# Garage_Controller.net
KiCad netlist of a schematic drawn in EAGLE
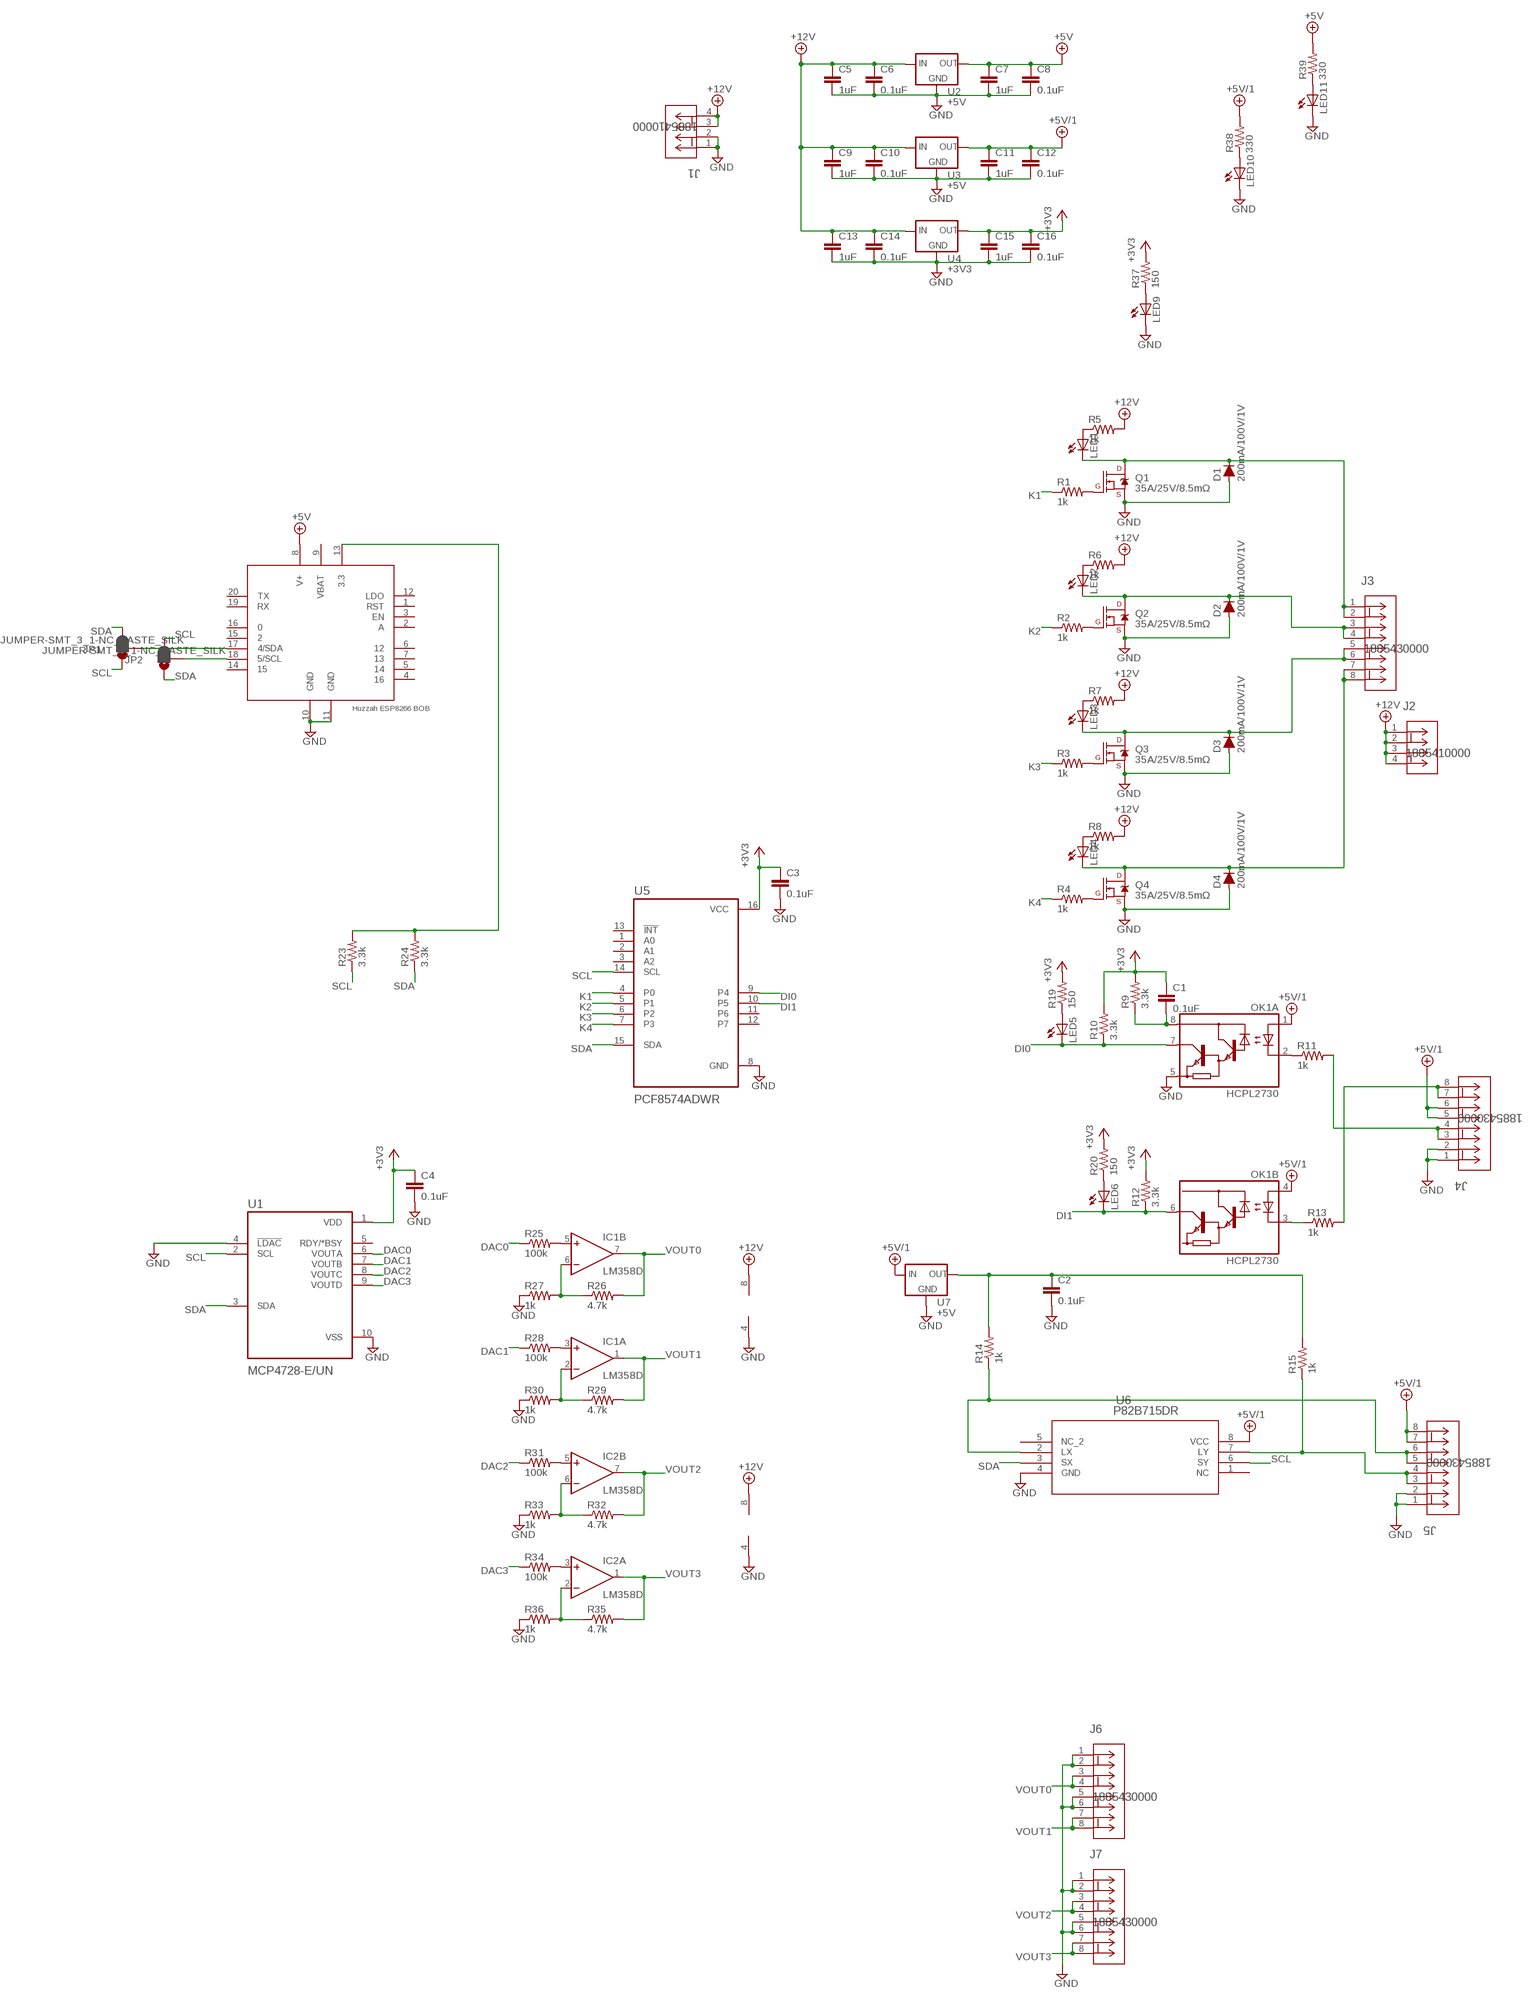
[diagram p0: schematic, sheet 1]

(export (version "E")
  (design (tool "Eeschema 10.0.6"))
  (components
    (comp (ref "C1")
      (value "0.1uF")
      (footprint "eagle-import:C0805")
      (libsource (lib "eagle-import") (part "C-EUC0805"))
    )
    (comp (ref "C2")
      (value "0.1uF")
      (footprint "eagle-import:C0805")
      (libsource (lib "eagle-import") (part "C-EUC0805"))
    )
    (comp (ref "C3")
      (value "0.1uF")
      (footprint "eagle-import:C0805")
      (libsource (lib "eagle-import") (part "C-EUC0805"))
    )
    (comp (ref "C4")
      (value "0.1uF")
      (footprint "eagle-import:C0805")
      (libsource (lib "eagle-import") (part "C-EUC0805"))
    )
    (comp (ref "C5")
      (value "1uF")
      (footprint "eagle-import:C0805")
      (libsource (lib "eagle-import") (part "C-EUC0805"))
    )
    (comp (ref "C6")
      (value "0.1uF")
      (footprint "eagle-import:C0805")
      (libsource (lib "eagle-import") (part "C-EUC0805"))
    )
    (comp (ref "C7")
      (value "1uF")
      (footprint "eagle-import:C0805")
      (libsource (lib "eagle-import") (part "C-EUC0805"))
    )
    (comp (ref "C8")
      (value "0.1uF")
      (footprint "eagle-import:C0805")
      (libsource (lib "eagle-import") (part "C-EUC0805"))
    )
    (comp (ref "C9")
      (value "1uF")
      (footprint "eagle-import:C0805")
      (libsource (lib "eagle-import") (part "C-EUC0805"))
    )
    (comp (ref "C10")
      (value "0.1uF")
      (footprint "eagle-import:C0805")
      (libsource (lib "eagle-import") (part "C-EUC0805"))
    )
    (comp (ref "C11")
      (value "1uF")
      (footprint "eagle-import:C0805")
      (libsource (lib "eagle-import") (part "C-EUC0805"))
    )
    (comp (ref "C12")
      (value "0.1uF")
      (footprint "eagle-import:C0805")
      (libsource (lib "eagle-import") (part "C-EUC0805"))
    )
    (comp (ref "C13")
      (value "1uF")
      (footprint "eagle-import:C0805")
      (libsource (lib "eagle-import") (part "C-EUC0805"))
    )
    (comp (ref "C14")
      (value "0.1uF")
      (footprint "eagle-import:C0805")
      (libsource (lib "eagle-import") (part "C-EUC0805"))
    )
    (comp (ref "C15")
      (value "1uF")
      (footprint "eagle-import:C0805")
      (libsource (lib "eagle-import") (part "C-EUC0805"))
    )
    (comp (ref "C16")
      (value "0.1uF")
      (footprint "eagle-import:C0805")
      (libsource (lib "eagle-import") (part "C-EUC0805"))
    )
    (comp (ref "D1")
      (value "200mA/100V/1V")
      (footprint "eagle-import:DIODE-1N4148")
      (libsource (lib "eagle-import") (part "DIODE-1N4148"))
    )
    (comp (ref "D2")
      (value "200mA/100V/1V")
      (footprint "eagle-import:DIODE-1N4148")
      (libsource (lib "eagle-import") (part "DIODE-1N4148"))
    )
    (comp (ref "D3")
      (value "200mA/100V/1V")
      (footprint "eagle-import:DIODE-1N4148")
      (libsource (lib "eagle-import") (part "DIODE-1N4148"))
    )
    (comp (ref "D4")
      (value "200mA/100V/1V")
      (footprint "eagle-import:DIODE-1N4148")
      (libsource (lib "eagle-import") (part "DIODE-1N4148"))
    )
    (comp (ref "IC1")
      (value "LM358D")
      (footprint "eagle-import:SO08")
      (libsource (lib "eagle-import") (part "LM358D"))
    )
    (comp (ref "IC2")
      (value "LM358D")
      (footprint "eagle-import:SO08")
      (libsource (lib "eagle-import") (part "LM358D"))
    )
    (comp (ref "J1")
      (value "1885410000")
      (footprint "eagle-import:CONN_1885410000_WED")
      (fields (field (name "COPYRIGHT") "Copyright (C) 2026 Ultra Librarian. All rights reserved."))
      (libsource (lib "eagle-import") (part "1885410000"))
    )
    (comp (ref "J2")
      (value "1885410000")
      (footprint "eagle-import:CONN_1885410000_WED")
      (fields (field (name "COPYRIGHT") "Copyright (C) 2026 Ultra Librarian. All rights reserved."))
      (libsource (lib "eagle-import") (part "1885410000"))
    )
    (comp (ref "J3")
      (value "1885430000")
      (footprint "eagle-import:CONN_1885430000_WED")
      (fields (field (name "COPYRIGHT") "Copyright (C) 2026 Ultra Librarian. All rights reserved."))
      (libsource (lib "eagle-import") (part "1885430000"))
    )
    (comp (ref "J4")
      (value "1885430000")
      (footprint "eagle-import:CONN_1885430000_WED")
      (fields (field (name "COPYRIGHT") "Copyright (C) 2026 Ultra Librarian. All rights reserved."))
      (libsource (lib "eagle-import") (part "1885430000"))
    )
    (comp (ref "J5")
      (value "1885430000")
      (footprint "eagle-import:CONN_1885430000_WED")
      (fields (field (name "COPYRIGHT") "Copyright (C) 2026 Ultra Librarian. All rights reserved."))
      (libsource (lib "eagle-import") (part "1885430000"))
    )
    (comp (ref "J6")
      (value "1885430000")
      (footprint "eagle-import:CONN_1885430000_WED")
      (fields (field (name "COPYRIGHT") "Copyright (C) 2026 Ultra Librarian. All rights reserved."))
      (libsource (lib "eagle-import") (part "1885430000"))
    )
    (comp (ref "J7")
      (value "1885430000")
      (footprint "eagle-import:CONN_1885430000_WED")
      (fields (field (name "COPYRIGHT") "Copyright (C) 2026 Ultra Librarian. All rights reserved."))
      (libsource (lib "eagle-import") (part "1885430000"))
    )
    (comp (ref "JP1")
      (value "JUMPER-SMT_3_1-NC_PASTE_SILK")
      (footprint "eagle-import:SMT-JUMPER_3_1-NC_PASTE_SILK")
      (libsource (lib "eagle-import") (part "JUMPER-SMT_3_1-NC_PASTE_SILK"))
    )
    (comp (ref "JP2")
      (value "JUMPER-SMT_3_1-NC_PASTE_SILK")
      (footprint "eagle-import:SMT-JUMPER_3_1-NC_PASTE_SILK")
      (libsource (lib "eagle-import") (part "JUMPER-SMT_3_1-NC_PASTE_SILK"))
    )
    (comp (ref "LED1")
      (value "LEDCHIP-LED0805")
      (footprint "eagle-import:CHIP-LED0805")
      (libsource (lib "eagle-import") (part "LEDCHIP-LED0805"))
    )
    (comp (ref "LED2")
      (value "LEDCHIP-LED0805")
      (footprint "eagle-import:CHIP-LED0805")
      (libsource (lib "eagle-import") (part "LEDCHIP-LED0805"))
    )
    (comp (ref "LED3")
      (value "LEDCHIP-LED0805")
      (footprint "eagle-import:CHIP-LED0805")
      (libsource (lib "eagle-import") (part "LEDCHIP-LED0805"))
    )
    (comp (ref "LED4")
      (value "LEDCHIP-LED0805")
      (footprint "eagle-import:CHIP-LED0805")
      (libsource (lib "eagle-import") (part "LEDCHIP-LED0805"))
    )
    (comp (ref "LED5")
      (value "LEDCHIP-LED0805")
      (footprint "eagle-import:CHIP-LED0805")
      (libsource (lib "eagle-import") (part "LEDCHIP-LED0805"))
    )
    (comp (ref "LED6")
      (value "LEDCHIP-LED0805")
      (footprint "eagle-import:CHIP-LED0805")
      (libsource (lib "eagle-import") (part "LEDCHIP-LED0805"))
    )
    (comp (ref "LED9")
      (value "LEDCHIP-LED0805")
      (footprint "eagle-import:CHIP-LED0805")
      (libsource (lib "eagle-import") (part "LEDCHIP-LED0805"))
    )
    (comp (ref "LED10")
      (value "LEDCHIP-LED0805")
      (footprint "eagle-import:CHIP-LED0805")
      (libsource (lib "eagle-import") (part "LEDCHIP-LED0805"))
    )
    (comp (ref "LED11")
      (value "LEDCHIP-LED0805")
      (footprint "eagle-import:CHIP-LED0805")
      (libsource (lib "eagle-import") (part "LEDCHIP-LED0805"))
    )
    (comp (ref "OK1")
      (value "HCPL2730")
      (footprint "eagle-import:DIL08")
      (fields (field (name "MF") "AGILENT TECHNOLOGIES") (field (name "MPN") "HCPL-2730-000E"))
      (libsource (lib "eagle-import") (part "HCPL2730"))
    )
    (comp (ref "Q1")
      (value "35A/25V/8.5mΩ")
      (footprint "eagle-import:TO-252_DPAK")
      (libsource (lib "eagle-import") (part "MOSFET-NCH-FDD8780"))
    )
    (comp (ref "Q2")
      (value "35A/25V/8.5mΩ")
      (footprint "eagle-import:TO-252_DPAK")
      (libsource (lib "eagle-import") (part "MOSFET-NCH-FDD8780"))
    )
    (comp (ref "Q3")
      (value "35A/25V/8.5mΩ")
      (footprint "eagle-import:TO-252_DPAK")
      (libsource (lib "eagle-import") (part "MOSFET-NCH-FDD8780"))
    )
    (comp (ref "Q4")
      (value "35A/25V/8.5mΩ")
      (footprint "eagle-import:TO-252_DPAK")
      (libsource (lib "eagle-import") (part "MOSFET-NCH-FDD8780"))
    )
    (comp (ref "R1")
      (value "1k")
      (footprint "eagle-import:R0805")
      (libsource (lib "eagle-import") (part "R-US_R0805"))
    )
    (comp (ref "R2")
      (value "1k")
      (footprint "eagle-import:R0805")
      (libsource (lib "eagle-import") (part "R-US_R0805"))
    )
    (comp (ref "R3")
      (value "1k")
      (footprint "eagle-import:R0805")
      (libsource (lib "eagle-import") (part "R-US_R0805"))
    )
    (comp (ref "R4")
      (value "1k")
      (footprint "eagle-import:R0805")
      (libsource (lib "eagle-import") (part "R-US_R0805"))
    )
    (comp (ref "R5")
      (value "1k")
      (footprint "eagle-import:R0805")
      (libsource (lib "eagle-import") (part "R-US_R0805"))
    )
    (comp (ref "R6")
      (value "1k")
      (footprint "eagle-import:R0805")
      (libsource (lib "eagle-import") (part "R-US_R0805"))
    )
    (comp (ref "R7")
      (value "1k")
      (footprint "eagle-import:R0805")
      (libsource (lib "eagle-import") (part "R-US_R0805"))
    )
    (comp (ref "R8")
      (value "1k")
      (footprint "eagle-import:R0805")
      (libsource (lib "eagle-import") (part "R-US_R0805"))
    )
    (comp (ref "R9")
      (value "3.3k")
      (footprint "eagle-import:R0805")
      (libsource (lib "eagle-import") (part "R-US_R0805"))
    )
    (comp (ref "R10")
      (value "3.3k")
      (footprint "eagle-import:R0805")
      (libsource (lib "eagle-import") (part "R-US_R0805"))
    )
    (comp (ref "R11")
      (value "1k")
      (footprint "eagle-import:R0805")
      (libsource (lib "eagle-import") (part "R-US_R0805"))
    )
    (comp (ref "R12")
      (value "3.3k")
      (footprint "eagle-import:R0805")
      (libsource (lib "eagle-import") (part "R-US_R0805"))
    )
    (comp (ref "R13")
      (value "1k")
      (footprint "eagle-import:R0805")
      (libsource (lib "eagle-import") (part "R-US_R0805"))
    )
    (comp (ref "R14")
      (value "1k")
      (footprint "eagle-import:R0805")
      (libsource (lib "eagle-import") (part "R-US_R0805"))
    )
    (comp (ref "R15")
      (value "1k")
      (footprint "eagle-import:R0805")
      (libsource (lib "eagle-import") (part "R-US_R0805"))
    )
    (comp (ref "R19")
      (value "150")
      (footprint "eagle-import:R0805")
      (libsource (lib "eagle-import") (part "R-US_R0805"))
    )
    (comp (ref "R20")
      (value "150")
      (footprint "eagle-import:R0805")
      (libsource (lib "eagle-import") (part "R-US_R0805"))
    )
    (comp (ref "R23")
      (value "3.3k")
      (footprint "eagle-import:R0805")
      (libsource (lib "eagle-import") (part "R-US_R0805"))
    )
    (comp (ref "R24")
      (value "3.3k")
      (footprint "eagle-import:R0805")
      (libsource (lib "eagle-import") (part "R-US_R0805"))
    )
    (comp (ref "R25")
      (value "100k")
      (footprint "eagle-import:R0805")
      (libsource (lib "eagle-import") (part "R-US_R0805"))
    )
    (comp (ref "R26")
      (value "4.7k")
      (footprint "eagle-import:R0805")
      (libsource (lib "eagle-import") (part "R-US_R0805"))
    )
    (comp (ref "R27")
      (value "1k")
      (footprint "eagle-import:R0805")
      (libsource (lib "eagle-import") (part "R-US_R0805"))
    )
    (comp (ref "R28")
      (value "100k")
      (footprint "eagle-import:R0805")
      (libsource (lib "eagle-import") (part "R-US_R0805"))
    )
    (comp (ref "R29")
      (value "4.7k")
      (footprint "eagle-import:R0805")
      (libsource (lib "eagle-import") (part "R-US_R0805"))
    )
    (comp (ref "R30")
      (value "1k")
      (footprint "eagle-import:R0805")
      (libsource (lib "eagle-import") (part "R-US_R0805"))
    )
    (comp (ref "R31")
      (value "100k")
      (footprint "eagle-import:R0805")
      (libsource (lib "eagle-import") (part "R-US_R0805"))
    )
    (comp (ref "R32")
      (value "4.7k")
      (footprint "eagle-import:R0805")
      (libsource (lib "eagle-import") (part "R-US_R0805"))
    )
    (comp (ref "R33")
      (value "1k")
      (footprint "eagle-import:R0805")
      (libsource (lib "eagle-import") (part "R-US_R0805"))
    )
    (comp (ref "R34")
      (value "100k")
      (footprint "eagle-import:R0805")
      (libsource (lib "eagle-import") (part "R-US_R0805"))
    )
    (comp (ref "R35")
      (value "4.7k")
      (footprint "eagle-import:R0805")
      (libsource (lib "eagle-import") (part "R-US_R0805"))
    )
    (comp (ref "R36")
      (value "1k")
      (footprint "eagle-import:R0805")
      (libsource (lib "eagle-import") (part "R-US_R0805"))
    )
    (comp (ref "R37")
      (value "150")
      (footprint "eagle-import:R0805")
      (libsource (lib "eagle-import") (part "R-US_R0805"))
    )
    (comp (ref "R38")
      (value "330")
      (footprint "eagle-import:R0805")
      (libsource (lib "eagle-import") (part "R-US_R0805"))
    )
    (comp (ref "R39")
      (value "330")
      (footprint "eagle-import:R0805")
      (libsource (lib "eagle-import") (part "R-US_R0805"))
    )
    (comp (ref "U$2")
      (value "HUZZAH_ESP8266_BREAKOUT")
      (footprint "eagle-import:HUZZAH_ESP8266_BREAKOUT")
      (libsource (lib "eagle-import") (part "HUZZAH_ESP8266_BREAKOUT"))
    )
    (comp (ref "U1")
      (value "MCP4728-E/UN")
      (footprint "eagle-import:SOP50P490X110-10N")
      (libsource (lib "eagle-import") (part "MCP4728-E/UN"))
    )
    (comp (ref "U2")
      (value "+5V")
      (footprint "eagle-import:TO-252")
      (libsource (lib "eagle-import") (part "V_REG_78XX7812"))
    )
    (comp (ref "U3")
      (value "+5V")
      (footprint "eagle-import:TO-252")
      (libsource (lib "eagle-import") (part "V_REG_78XX7812"))
    )
    (comp (ref "U4")
      (value "+3V3")
      (footprint "eagle-import:TO-252")
      (libsource (lib "eagle-import") (part "V_REG_78XX7812"))
    )
    (comp (ref "U5")
      (value "PCF8574ADWR")
      (footprint "eagle-import:SOIC127P1030X265-16N")
      (libsource (lib "eagle-import") (part "PCF8574ADWR"))
    )
    (comp (ref "U6")
      (value "P82B715DR")
      (footprint "eagle-import:SO-08")
      (libsource (lib "eagle-import") (part "P82B715DR"))
    )
    (comp (ref "U7")
      (value "+5V")
      (footprint "eagle-import:TO-252")
      (libsource (lib "eagle-import") (part "V_REG_78XX7812"))
    )
  )
  (nets
    (net (code "1") (name "+3V3") (class "Default")
      (node (ref "C1") (pin "1") (pinfunction "1_1") (pintype "passive"))
      (node (ref "C15") (pin "1") (pinfunction "1_1") (pintype "passive"))
      (node (ref "C16") (pin "1") (pinfunction "1_1") (pintype "passive"))
      (node (ref "C3") (pin "1") (pinfunction "1_1") (pintype "passive"))
      (node (ref "C4") (pin "1") (pinfunction "1_1") (pintype "passive"))
      (node (ref "R10") (pin "2") (pinfunction "2_2") (pintype "passive"))
      (node (ref "R12") (pin "2") (pinfunction "2_2") (pintype "passive"))
      (node (ref "R19") (pin "2") (pinfunction "2_2") (pintype "passive"))
      (node (ref "R20") (pin "2") (pinfunction "2_2") (pintype "passive"))
      (node (ref "R37") (pin "2") (pinfunction "2_2") (pintype "passive"))
      (node (ref "R9") (pin "2") (pinfunction "2_2") (pintype "passive"))
      (node (ref "U1") (pin "1") (pinfunction "VDD_1") (pintype "power_in"))
      (node (ref "U4") (pin "2") (pinfunction "OUT_2") (pintype "passive"))
      (node (ref "U5") (pin "16") (pinfunction "VCC_16") (pintype "power_in"))
    )
    (net (code "2") (name "+5V") (class "Default")
      (node (ref "C7") (pin "1") (pinfunction "1_1") (pintype "passive"))
      (node (ref "C8") (pin "1") (pinfunction "1_1") (pintype "passive"))
      (node (ref "R39") (pin "2") (pinfunction "2_2") (pintype "passive"))
      (node (ref "U$2") (pin "8") (pinfunction "V+_8") (pintype "power_in"))
      (node (ref "U2") (pin "2") (pinfunction "OUT_2") (pintype "passive"))
    )
    (net (code "3") (name "+5V{slash}1") (class "Default")
      (node (ref "C11") (pin "1") (pinfunction "1_1") (pintype "passive"))
      (node (ref "C12") (pin "1") (pinfunction "1_1") (pintype "passive"))
      (node (ref "J4") (pin "5") (pinfunction "5_5") (pintype "passive"))
      (node (ref "J4") (pin "6") (pinfunction "6_6") (pintype "passive"))
      (node (ref "J5") (pin "7") (pinfunction "7_7") (pintype "passive"))
      (node (ref "J5") (pin "8") (pinfunction "8_8") (pintype "passive"))
      (node (ref "OK1") (pin "1") (pinfunction "A1_1") (pintype "passive"))
      (node (ref "OK1") (pin "4") (pinfunction "A2_4") (pintype "passive"))
      (node (ref "R38") (pin "2") (pinfunction "2_2") (pintype "passive"))
      (node (ref "U3") (pin "2") (pinfunction "OUT_2") (pintype "passive"))
      (node (ref "U6") (pin "8") (pinfunction "VCC_8") (pintype "power_in"))
      (node (ref "U7") (pin "1") (pinfunction "IN_1") (pintype "input"))
    )
    (net (code "4") (name "+12V") (class "Default")
      (node (ref "C10") (pin "1") (pinfunction "1_1") (pintype "passive"))
      (node (ref "C13") (pin "1") (pinfunction "1_1") (pintype "passive"))
      (node (ref "C14") (pin "1") (pinfunction "1_1") (pintype "passive"))
      (node (ref "C5") (pin "1") (pinfunction "1_1") (pintype "passive"))
      (node (ref "C6") (pin "1") (pinfunction "1_1") (pintype "passive"))
      (node (ref "C9") (pin "1") (pinfunction "1_1") (pintype "passive"))
      (node (ref "IC1") (pin "8") (pinfunction "V+_8") (pintype "power_in"))
      (node (ref "IC2") (pin "8") (pinfunction "V+_8") (pintype "power_in"))
      (node (ref "J1") (pin "3") (pinfunction "3_3") (pintype "passive"))
      (node (ref "J1") (pin "4") (pinfunction "4_4") (pintype "passive"))
      (node (ref "J2") (pin "1") (pinfunction "1_1") (pintype "passive"))
      (node (ref "J2") (pin "2") (pinfunction "2_2") (pintype "passive"))
      (node (ref "J2") (pin "3") (pinfunction "3_3") (pintype "passive"))
      (node (ref "J2") (pin "4") (pinfunction "4_4") (pintype "passive"))
      (node (ref "R5") (pin "2") (pinfunction "2_2") (pintype "passive"))
      (node (ref "R6") (pin "2") (pinfunction "2_2") (pintype "passive"))
      (node (ref "R7") (pin "2") (pinfunction "2_2") (pintype "passive"))
      (node (ref "R8") (pin "2") (pinfunction "2_2") (pintype "passive"))
      (node (ref "U2") (pin "1") (pinfunction "IN_1") (pintype "input"))
      (node (ref "U3") (pin "1") (pinfunction "IN_1") (pintype "input"))
      (node (ref "U4") (pin "1") (pinfunction "IN_1") (pintype "input"))
    )
    (net (code "5") (name "/DAC0") (class "Default")
      (node (ref "R25") (pin "1") (pinfunction "1_1") (pintype "passive"))
      (node (ref "U1") (pin "6") (pinfunction "VOUTA_6") (pintype "output"))
    )
    (net (code "6") (name "/DAC1") (class "Default")
      (node (ref "R28") (pin "1") (pinfunction "1_1") (pintype "passive"))
      (node (ref "U1") (pin "7") (pinfunction "VOUTB_7") (pintype "output"))
    )
    (net (code "7") (name "/DAC2") (class "Default")
      (node (ref "R31") (pin "1") (pinfunction "1_1") (pintype "passive"))
      (node (ref "U1") (pin "8") (pinfunction "VOUTC_8") (pintype "output"))
    )
    (net (code "8") (name "/DAC3") (class "Default")
      (node (ref "R34") (pin "1") (pinfunction "1_1") (pintype "passive"))
      (node (ref "U1") (pin "9") (pinfunction "VOUTD_9") (pintype "output"))
    )
    (net (code "9") (name "/DI0") (class "Default")
      (node (ref "LED5") (pin "C") (pinfunction "C_C") (pintype "passive"))
      (node (ref "OK1") (pin "7") (pinfunction "VO1_7") (pintype "passive"))
      (node (ref "R10") (pin "1") (pinfunction "1_1") (pintype "passive"))
      (node (ref "U5") (pin "9") (pinfunction "P4_9") (pintype "bidirectional"))
    )
    (net (code "10") (name "/DI1") (class "Default")
      (node (ref "LED6") (pin "C") (pinfunction "C_C") (pintype "passive"))
      (node (ref "OK1") (pin "6") (pinfunction "VO2_6") (pintype "passive"))
      (node (ref "R12") (pin "1") (pinfunction "1_1") (pintype "passive"))
      (node (ref "U5") (pin "10") (pinfunction "P5_10") (pintype "bidirectional"))
    )
    (net (code "11") (name "/K1") (class "Default")
      (node (ref "R1") (pin "1") (pinfunction "1_1") (pintype "passive"))
      (node (ref "U5") (pin "4") (pinfunction "P0_4") (pintype "bidirectional"))
    )
    (net (code "12") (name "/K2") (class "Default")
      (node (ref "R2") (pin "1") (pinfunction "1_1") (pintype "passive"))
      (node (ref "U5") (pin "5") (pinfunction "P1_5") (pintype "bidirectional"))
    )
    (net (code "13") (name "/K3") (class "Default")
      (node (ref "R3") (pin "1") (pinfunction "1_1") (pintype "passive"))
      (node (ref "U5") (pin "6") (pinfunction "P2_6") (pintype "bidirectional"))
    )
    (net (code "14") (name "/K4") (class "Default")
      (node (ref "R4") (pin "1") (pinfunction "1_1") (pintype "passive"))
      (node (ref "U5") (pin "7") (pinfunction "P3_7") (pintype "bidirectional"))
    )
    (net (code "15") (name "/SCL") (class "Default")
      (node (ref "JP1") (pin "1") (pinfunction "1_1") (pintype "passive"))
      (node (ref "JP2") (pin "3") (pinfunction "3_3") (pintype "passive"))
      (node (ref "R23") (pin "1") (pinfunction "1_1") (pintype "passive"))
      (node (ref "U1") (pin "2") (pinfunction "SCL_2") (pintype "input"))
      (node (ref "U5") (pin "14") (pinfunction "SCL_14") (pintype "input"))
      (node (ref "U6") (pin "6") (pinfunction "SY_6") (pintype "passive"))
    )
    (net (code "16") (name "/SDA") (class "Default")
      (node (ref "JP1") (pin "3") (pinfunction "3_3") (pintype "passive"))
      (node (ref "JP2") (pin "1") (pinfunction "1_1") (pintype "passive"))
      (node (ref "R24") (pin "1") (pinfunction "1_1") (pintype "passive"))
      (node (ref "U1") (pin "3") (pinfunction "SDA_3") (pintype "bidirectional"))
      (node (ref "U5") (pin "15") (pinfunction "SDA_15") (pintype "bidirectional"))
      (node (ref "U6") (pin "3") (pinfunction "SX_3") (pintype "passive"))
    )
    (net (code "17") (name "/VBAT") (class "Default")
      (node (ref "U$2") (pin "9") (pinfunction "VBAT_9") (pintype "power_in"))
    )
    (net (code "18") (name "/VOUT0") (class "Default")
      (node (ref "IC1") (pin "7") (pinfunction "OUT_7") (pintype "output"))
      (node (ref "J6") (pin "3") (pinfunction "3_3") (pintype "passive"))
      (node (ref "J6") (pin "4") (pinfunction "4_4") (pintype "passive"))
      (node (ref "R26") (pin "2") (pinfunction "2_2") (pintype "passive"))
    )
    (net (code "19") (name "/VOUT1") (class "Default")
      (node (ref "IC1") (pin "1") (pinfunction "OUT_1") (pintype "output"))
      (node (ref "J6") (pin "7") (pinfunction "7_7") (pintype "passive"))
      (node (ref "J6") (pin "8") (pinfunction "8_8") (pintype "passive"))
      (node (ref "R29") (pin "2") (pinfunction "2_2") (pintype "passive"))
    )
    (net (code "20") (name "/VOUT2") (class "Default")
      (node (ref "IC2") (pin "7") (pinfunction "OUT_7") (pintype "output"))
      (node (ref "J7") (pin "3") (pinfunction "3_3") (pintype "passive"))
      (node (ref "J7") (pin "4") (pinfunction "4_4") (pintype "passive"))
      (node (ref "R32") (pin "2") (pinfunction "2_2") (pintype "passive"))
    )
    (net (code "21") (name "/VOUT3") (class "Default")
      (node (ref "IC2") (pin "1") (pinfunction "OUT_1") (pintype "output"))
      (node (ref "J7") (pin "7") (pinfunction "7_7") (pintype "passive"))
      (node (ref "J7") (pin "8") (pinfunction "8_8") (pintype "passive"))
      (node (ref "R35") (pin "2") (pinfunction "2_2") (pintype "passive"))
    )
    (net (code "22") (name "GND") (class "Default")
      (node (ref "C10") (pin "2") (pinfunction "2_2") (pintype "passive"))
      (node (ref "C11") (pin "2") (pinfunction "2_2") (pintype "passive"))
      (node (ref "C12") (pin "2") (pinfunction "2_2") (pintype "passive"))
      (node (ref "C13") (pin "2") (pinfunction "2_2") (pintype "passive"))
      (node (ref "C14") (pin "2") (pinfunction "2_2") (pintype "passive"))
      (node (ref "C15") (pin "2") (pinfunction "2_2") (pintype "passive"))
      (node (ref "C16") (pin "2") (pinfunction "2_2") (pintype "passive"))
      (node (ref "C2") (pin "2") (pinfunction "2_2") (pintype "passive"))
      (node (ref "C3") (pin "2") (pinfunction "2_2") (pintype "passive"))
      (node (ref "C4") (pin "2") (pinfunction "2_2") (pintype "passive"))
      (node (ref "C5") (pin "2") (pinfunction "2_2") (pintype "passive"))
      (node (ref "C6") (pin "2") (pinfunction "2_2") (pintype "passive"))
      (node (ref "C7") (pin "2") (pinfunction "2_2") (pintype "passive"))
      (node (ref "C8") (pin "2") (pinfunction "2_2") (pintype "passive"))
      (node (ref "C9") (pin "2") (pinfunction "2_2") (pintype "passive"))
      (node (ref "D1") (pin "A") (pinfunction "A_A") (pintype "passive"))
      (node (ref "D2") (pin "A") (pinfunction "A_A") (pintype "passive"))
      (node (ref "D3") (pin "A") (pinfunction "A_A") (pintype "passive"))
      (node (ref "D4") (pin "A") (pinfunction "A_A") (pintype "passive"))
      (node (ref "IC1") (pin "4") (pinfunction "V-_4") (pintype "power_in"))
      (node (ref "IC2") (pin "4") (pinfunction "V-_4") (pintype "power_in"))
      (node (ref "J1") (pin "1") (pinfunction "1_1") (pintype "passive"))
      (node (ref "J1") (pin "2") (pinfunction "2_2") (pintype "passive"))
      (node (ref "J4") (pin "1") (pinfunction "1_1") (pintype "passive"))
      (node (ref "J4") (pin "2") (pinfunction "2_2") (pintype "passive"))
      (node (ref "J5") (pin "1") (pinfunction "1_1") (pintype "passive"))
      (node (ref "J5") (pin "2") (pinfunction "2_2") (pintype "passive"))
      (node (ref "J6") (pin "1") (pinfunction "1_1") (pintype "passive"))
      (node (ref "J6") (pin "2") (pinfunction "2_2") (pintype "passive"))
      (node (ref "J6") (pin "5") (pinfunction "5_5") (pintype "passive"))
      (node (ref "J6") (pin "6") (pinfunction "6_6") (pintype "passive"))
      (node (ref "J7") (pin "1") (pinfunction "1_1") (pintype "passive"))
      (node (ref "J7") (pin "2") (pinfunction "2_2") (pintype "passive"))
      (node (ref "J7") (pin "5") (pinfunction "5_5") (pintype "passive"))
      (node (ref "J7") (pin "6") (pinfunction "6_6") (pintype "passive"))
      (node (ref "LED10") (pin "C") (pinfunction "C_C") (pintype "passive"))
      (node (ref "LED11") (pin "C") (pinfunction "C_C") (pintype "passive"))
      (node (ref "LED9") (pin "C") (pinfunction "C_C") (pintype "passive"))
      (node (ref "OK1") (pin "5") (pinfunction "GND_5") (pintype "passive"))
      (node (ref "Q1") (pin "3") (pinfunction "S_3") (pintype "bidirectional"))
      (node (ref "Q2") (pin "3") (pinfunction "S_3") (pintype "bidirectional"))
      (node (ref "Q3") (pin "3") (pinfunction "S_3") (pintype "bidirectional"))
      (node (ref "Q4") (pin "3") (pinfunction "S_3") (pintype "bidirectional"))
      (node (ref "R27") (pin "1") (pinfunction "1_1") (pintype "passive"))
      (node (ref "R30") (pin "1") (pinfunction "1_1") (pintype "passive"))
      (node (ref "R33") (pin "1") (pinfunction "1_1") (pintype "passive"))
      (node (ref "R36") (pin "1") (pinfunction "1_1") (pintype "passive"))
      (node (ref "U$2") (pin "10") (pinfunction "GND_10") (pintype "power_in"))
      (node (ref "U$2") (pin "11") (pinfunction "GND_11") (pintype "power_in"))
      (node (ref "U1") (pin "10") (pinfunction "VSS_10") (pintype "power_in"))
      (node (ref "U1") (pin "4") (pinfunction "~{LDAC}_4") (pintype "input"))
      (node (ref "U2") (pin "3") (pinfunction "GND_3") (pintype "input"))
      (node (ref "U3") (pin "3") (pinfunction "GND_3") (pintype "input"))
      (node (ref "U4") (pin "3") (pinfunction "GND_3") (pintype "input"))
      (node (ref "U5") (pin "8") (pinfunction "GND_8") (pintype "power_in"))
      (node (ref "U6") (pin "4") (pinfunction "GND_4") (pintype "power_in"))
      (node (ref "U7") (pin "3") (pinfunction "GND_3") (pintype "input"))
    )
    (net (code "23") (name "Net-(IC1A-+IN)") (class "Default")
      (node (ref "IC1") (pin "3") (pinfunction "+IN_3") (pintype "input"))
      (node (ref "R28") (pin "2") (pinfunction "2_2") (pintype "passive"))
    )
    (net (code "24") (name "Net-(IC1A--IN)") (class "Default")
      (node (ref "IC1") (pin "2") (pinfunction "-IN_2") (pintype "input"))
      (node (ref "R29") (pin "1") (pinfunction "1_1") (pintype "passive"))
      (node (ref "R30") (pin "2") (pinfunction "2_2") (pintype "passive"))
    )
    (net (code "25") (name "Net-(IC1B-+IN)") (class "Default")
      (node (ref "IC1") (pin "5") (pinfunction "+IN_5") (pintype "input"))
      (node (ref "R25") (pin "2") (pinfunction "2_2") (pintype "passive"))
    )
    (net (code "26") (name "Net-(IC1B--IN)") (class "Default")
      (node (ref "IC1") (pin "6") (pinfunction "-IN_6") (pintype "input"))
      (node (ref "R26") (pin "1") (pinfunction "1_1") (pintype "passive"))
      (node (ref "R27") (pin "2") (pinfunction "2_2") (pintype "passive"))
    )
    (net (code "27") (name "Net-(IC2A-+IN)") (class "Default")
      (node (ref "IC2") (pin "3") (pinfunction "+IN_3") (pintype "input"))
      (node (ref "R34") (pin "2") (pinfunction "2_2") (pintype "passive"))
    )
    (net (code "28") (name "Net-(IC2A--IN)") (class "Default")
      (node (ref "IC2") (pin "2") (pinfunction "-IN_2") (pintype "input"))
      (node (ref "R35") (pin "1") (pinfunction "1_1") (pintype "passive"))
      (node (ref "R36") (pin "2") (pinfunction "2_2") (pintype "passive"))
    )
    (net (code "29") (name "Net-(IC2B-+IN)") (class "Default")
      (node (ref "IC2") (pin "5") (pinfunction "+IN_5") (pintype "input"))
      (node (ref "R31") (pin "2") (pinfunction "2_2") (pintype "passive"))
    )
    (net (code "30") (name "Net-(IC2B--IN)") (class "Default")
      (node (ref "IC2") (pin "6") (pinfunction "-IN_6") (pintype "input"))
      (node (ref "R32") (pin "1") (pinfunction "1_1") (pintype "passive"))
      (node (ref "R33") (pin "2") (pinfunction "2_2") (pintype "passive"))
    )
    (net (code "31") (name "Net-(J4-Pad3)") (class "Default")
      (node (ref "J4") (pin "3") (pinfunction "3_3") (pintype "passive"))
      (node (ref "J4") (pin "4") (pinfunction "4_4") (pintype "passive"))
      (node (ref "R11") (pin "2") (pinfunction "2_2") (pintype "passive"))
    )
    (net (code "32") (name "Net-(J4-Pad7)") (class "Default")
      (node (ref "J4") (pin "7") (pinfunction "7_7") (pintype "passive"))
      (node (ref "J4") (pin "8") (pinfunction "8_8") (pintype "passive"))
      (node (ref "R13") (pin "2") (pinfunction "2_2") (pintype "passive"))
    )
    (net (code "33") (name "Net-(LED1-PadA)") (class "Default")
      (node (ref "LED1") (pin "A") (pinfunction "A_A") (pintype "passive"))
      (node (ref "R5") (pin "1") (pinfunction "1_1") (pintype "passive"))
    )
    (net (code "34") (name "Net-(LED2-PadA)") (class "Default")
      (node (ref "LED2") (pin "A") (pinfunction "A_A") (pintype "passive"))
      (node (ref "R6") (pin "1") (pinfunction "1_1") (pintype "passive"))
    )
    (net (code "35") (name "Net-(LED3-PadA)") (class "Default")
      (node (ref "LED3") (pin "A") (pinfunction "A_A") (pintype "passive"))
      (node (ref "R7") (pin "1") (pinfunction "1_1") (pintype "passive"))
    )
    (net (code "36") (name "Net-(LED4-PadA)") (class "Default")
      (node (ref "LED4") (pin "A") (pinfunction "A_A") (pintype "passive"))
      (node (ref "R8") (pin "1") (pinfunction "1_1") (pintype "passive"))
    )
    (net (code "37") (name "Net-(LED5-PadA)") (class "Default")
      (node (ref "LED5") (pin "A") (pinfunction "A_A") (pintype "passive"))
      (node (ref "R19") (pin "1") (pinfunction "1_1") (pintype "passive"))
    )
    (net (code "38") (name "Net-(LED6-PadA)") (class "Default")
      (node (ref "LED6") (pin "A") (pinfunction "A_A") (pintype "passive"))
      (node (ref "R20") (pin "1") (pinfunction "1_1") (pintype "passive"))
    )
    (net (code "39") (name "Net-(LED9-PadA)") (class "Default")
      (node (ref "LED9") (pin "A") (pinfunction "A_A") (pintype "passive"))
      (node (ref "R37") (pin "1") (pinfunction "1_1") (pintype "passive"))
    )
    (net (code "40") (name "Net-(LED10-PadA)") (class "Default")
      (node (ref "LED10") (pin "A") (pinfunction "A_A") (pintype "passive"))
      (node (ref "R38") (pin "1") (pinfunction "1_1") (pintype "passive"))
    )
    (net (code "41") (name "Net-(LED11-PadA)") (class "Default")
      (node (ref "LED11") (pin "A") (pinfunction "A_A") (pintype "passive"))
      (node (ref "R39") (pin "1") (pinfunction "1_1") (pintype "passive"))
    )
    (net (code "42") (name "Net-(OK1A-C1)") (class "Default")
      (node (ref "OK1") (pin "2") (pinfunction "C1_2") (pintype "passive"))
      (node (ref "R11") (pin "1") (pinfunction "1_1") (pintype "passive"))
    )
    (net (code "43") (name "Net-(OK1A-VCC)") (class "Default")
      (node (ref "C1") (pin "2") (pinfunction "2_2") (pintype "passive"))
      (node (ref "OK1") (pin "8") (pinfunction "VCC_8") (pintype "passive"))
      (node (ref "R9") (pin "1") (pinfunction "1_1") (pintype "passive"))
    )
    (net (code "44") (name "Net-(OK1B-C2)") (class "Default")
      (node (ref "OK1") (pin "3") (pinfunction "C2_3") (pintype "passive"))
      (node (ref "R13") (pin "1") (pinfunction "1_1") (pintype "passive"))
    )
    (net (code "45") (name "Net-(Q1-D)") (class "Default")
      (node (ref "D1") (pin "C") (pinfunction "C_C") (pintype "passive"))
      (node (ref "J3") (pin "1") (pinfunction "1_1") (pintype "passive"))
      (node (ref "J3") (pin "2") (pinfunction "2_2") (pintype "passive"))
      (node (ref "LED1") (pin "C") (pinfunction "C_C") (pintype "passive"))
      (node (ref "Q1") (pin "2") (pinfunction "D_2") (pintype "bidirectional"))
    )
    (net (code "46") (name "Net-(Q1-G)") (class "Default")
      (node (ref "Q1") (pin "1") (pinfunction "G_1") (pintype "bidirectional"))
      (node (ref "R1") (pin "2") (pinfunction "2_2") (pintype "passive"))
    )
    (net (code "47") (name "Net-(Q2-D)") (class "Default")
      (node (ref "D2") (pin "C") (pinfunction "C_C") (pintype "passive"))
      (node (ref "J3") (pin "3") (pinfunction "3_3") (pintype "passive"))
      (node (ref "J3") (pin "4") (pinfunction "4_4") (pintype "passive"))
      (node (ref "LED2") (pin "C") (pinfunction "C_C") (pintype "passive"))
      (node (ref "Q2") (pin "2") (pinfunction "D_2") (pintype "bidirectional"))
    )
    (net (code "48") (name "Net-(Q2-G)") (class "Default")
      (node (ref "Q2") (pin "1") (pinfunction "G_1") (pintype "bidirectional"))
      (node (ref "R2") (pin "2") (pinfunction "2_2") (pintype "passive"))
    )
    (net (code "49") (name "Net-(Q3-D)") (class "Default")
      (node (ref "D3") (pin "C") (pinfunction "C_C") (pintype "passive"))
      (node (ref "J3") (pin "5") (pinfunction "5_5") (pintype "passive"))
      (node (ref "J3") (pin "6") (pinfunction "6_6") (pintype "passive"))
      (node (ref "LED3") (pin "C") (pinfunction "C_C") (pintype "passive"))
      (node (ref "Q3") (pin "2") (pinfunction "D_2") (pintype "bidirectional"))
    )
    (net (code "50") (name "Net-(Q3-G)") (class "Default")
      (node (ref "Q3") (pin "1") (pinfunction "G_1") (pintype "bidirectional"))
      (node (ref "R3") (pin "2") (pinfunction "2_2") (pintype "passive"))
    )
    (net (code "51") (name "Net-(Q4-D)") (class "Default")
      (node (ref "D4") (pin "C") (pinfunction "C_C") (pintype "passive"))
      (node (ref "J3") (pin "7") (pinfunction "7_7") (pintype "passive"))
      (node (ref "J3") (pin "8") (pinfunction "8_8") (pintype "passive"))
      (node (ref "LED4") (pin "C") (pinfunction "C_C") (pintype "passive"))
      (node (ref "Q4") (pin "2") (pinfunction "D_2") (pintype "bidirectional"))
    )
    (net (code "52") (name "Net-(Q4-G)") (class "Default")
      (node (ref "Q4") (pin "1") (pinfunction "G_1") (pintype "bidirectional"))
      (node (ref "R4") (pin "2") (pinfunction "2_2") (pintype "passive"))
    )
    (net (code "53") (name "Net-(U$2-3.3)") (class "Default")
      (node (ref "R23") (pin "2") (pinfunction "2_2") (pintype "passive"))
      (node (ref "R24") (pin "2") (pinfunction "2_2") (pintype "passive"))
      (node (ref "U$2") (pin "13") (pinfunction "3.3_13") (pintype "power_in"))
    )
    (net (code "54") (name "Net-(U$2-4{slash}SDA)") (class "Default")
      (node (ref "JP1") (pin "2") (pinfunction "2_2") (pintype "passive"))
      (node (ref "U$2") (pin "17") (pinfunction "4/SDA_17") (pintype "bidirectional"))
    )
    (net (code "55") (name "Net-(U$2-5{slash}SCL)") (class "Default")
      (node (ref "JP2") (pin "2") (pinfunction "2_2") (pintype "passive"))
      (node (ref "U$2") (pin "18") (pinfunction "5/SCL_18") (pintype "bidirectional"))
    )
    (net (code "56") (name "Net-(U6-LX)") (class "Default")
      (node (ref "J5") (pin "5") (pinfunction "5_5") (pintype "passive"))
      (node (ref "J5") (pin "6") (pinfunction "6_6") (pintype "passive"))
      (node (ref "R14") (pin "1") (pinfunction "1_1") (pintype "passive"))
      (node (ref "U6") (pin "2") (pinfunction "LX_2") (pintype "passive"))
    )
    (net (code "57") (name "Net-(U6-LY)") (class "Default")
      (node (ref "J5") (pin "3") (pinfunction "3_3") (pintype "passive"))
      (node (ref "J5") (pin "4") (pinfunction "4_4") (pintype "passive"))
      (node (ref "R15") (pin "1") (pinfunction "1_1") (pintype "passive"))
      (node (ref "U6") (pin "7") (pinfunction "LY_7") (pintype "passive"))
    )
    (net (code "58") (name "Net-(U7-OUT)") (class "Default")
      (node (ref "C2") (pin "1") (pinfunction "1_1") (pintype "passive"))
      (node (ref "R14") (pin "2") (pinfunction "2_2") (pintype "passive"))
      (node (ref "R15") (pin "2") (pinfunction "2_2") (pintype "passive"))
      (node (ref "U7") (pin "2") (pinfunction "OUT_2") (pintype "passive"))
    )
    (net (code "59") (name "unconnected-(U$2-0-Pad16)") (class "Default")
      (node (ref "U$2") (pin "16") (pinfunction "0_16") (pintype "bidirectional"))
    )
    (net (code "60") (name "unconnected-(U$2-2-Pad15)") (class "Default")
      (node (ref "U$2") (pin "15") (pinfunction "2_15") (pintype "bidirectional"))
    )
    (net (code "61") (name "unconnected-(U$2-12-Pad6)") (class "Default")
      (node (ref "U$2") (pin "6") (pinfunction "12_6") (pintype "bidirectional"))
    )
    (net (code "62") (name "unconnected-(U$2-13-Pad7)") (class "Default")
      (node (ref "U$2") (pin "7") (pinfunction "13_7") (pintype "bidirectional"))
    )
    (net (code "63") (name "unconnected-(U$2-14-Pad5)") (class "Default")
      (node (ref "U$2") (pin "5") (pinfunction "14_5") (pintype "bidirectional"))
    )
    (net (code "64") (name "unconnected-(U$2-15-Pad14)") (class "Default")
      (node (ref "U$2") (pin "14") (pinfunction "15_14") (pintype "bidirectional"))
    )
    (net (code "65") (name "unconnected-(U$2-16-Pad4)") (class "Default")
      (node (ref "U$2") (pin "4") (pinfunction "16_4") (pintype "bidirectional"))
    )
    (net (code "66") (name "unconnected-(U$2-A-Pad2)") (class "Default")
      (node (ref "U$2") (pin "2") (pinfunction "A_2") (pintype "passive"))
    )
    (net (code "67") (name "unconnected-(U$2-EN-Pad3)") (class "Default")
      (node (ref "U$2") (pin "3") (pinfunction "EN_3") (pintype "input"))
    )
    (net (code "68") (name "unconnected-(U$2-LDO-Pad12)") (class "Default")
      (node (ref "U$2") (pin "12") (pinfunction "LDO_12") (pintype "input"))
    )
    (net (code "69") (name "unconnected-(U$2-RST-Pad1)") (class "Default")
      (node (ref "U$2") (pin "1") (pinfunction "RST_1") (pintype "input"))
    )
    (net (code "70") (name "unconnected-(U$2-RX-Pad19)") (class "Default")
      (node (ref "U$2") (pin "19") (pinfunction "RX_19") (pintype "input"))
    )
    (net (code "71") (name "unconnected-(U$2-TX-Pad20)") (class "Default")
      (node (ref "U$2") (pin "20") (pinfunction "TX_20") (pintype "output"))
    )
    (net (code "72") (name "unconnected-(U1-RDY{slash}*BSY-Pad5)") (class "Default")
      (node (ref "U1") (pin "5") (pinfunction "RDY/*BSY_5") (pintype "output"))
    )
    (net (code "73") (name "unconnected-(U5-A0-Pad1)") (class "Default")
      (node (ref "U5") (pin "1") (pinfunction "A0_1") (pintype "input"))
    )
    (net (code "74") (name "unconnected-(U5-A1-Pad2)") (class "Default")
      (node (ref "U5") (pin "2") (pinfunction "A1_2") (pintype "input"))
    )
    (net (code "75") (name "unconnected-(U5-A2-Pad3)") (class "Default")
      (node (ref "U5") (pin "3") (pinfunction "A2_3") (pintype "input"))
    )
    (net (code "76") (name "unconnected-(U5-P6-Pad11)") (class "Default")
      (node (ref "U5") (pin "11") (pinfunction "P6_11") (pintype "bidirectional"))
    )
    (net (code "77") (name "unconnected-(U5-P7-Pad12)") (class "Default")
      (node (ref "U5") (pin "12") (pinfunction "P7_12") (pintype "bidirectional"))
    )
    (net (code "78") (name "unconnected-(U5-~{INT}-Pad13)") (class "Default")
      (node (ref "U5") (pin "13") (pinfunction "~{INT}_13") (pintype "input"))
    )
    (net (code "79") (name "unconnected-(U6-NC-Pad1)") (class "Default")
      (node (ref "U6") (pin "1") (pinfunction "NC_1") (pintype "passive"))
    )
    (net (code "80") (name "unconnected-(U6-NC_2-Pad5)") (class "Default")
      (node (ref "U6") (pin "5") (pinfunction "NC_2_5") (pintype "passive"))
    )
  )
)
